# communication.net
KiCad netlist of a schematic drawn in Altium Designer
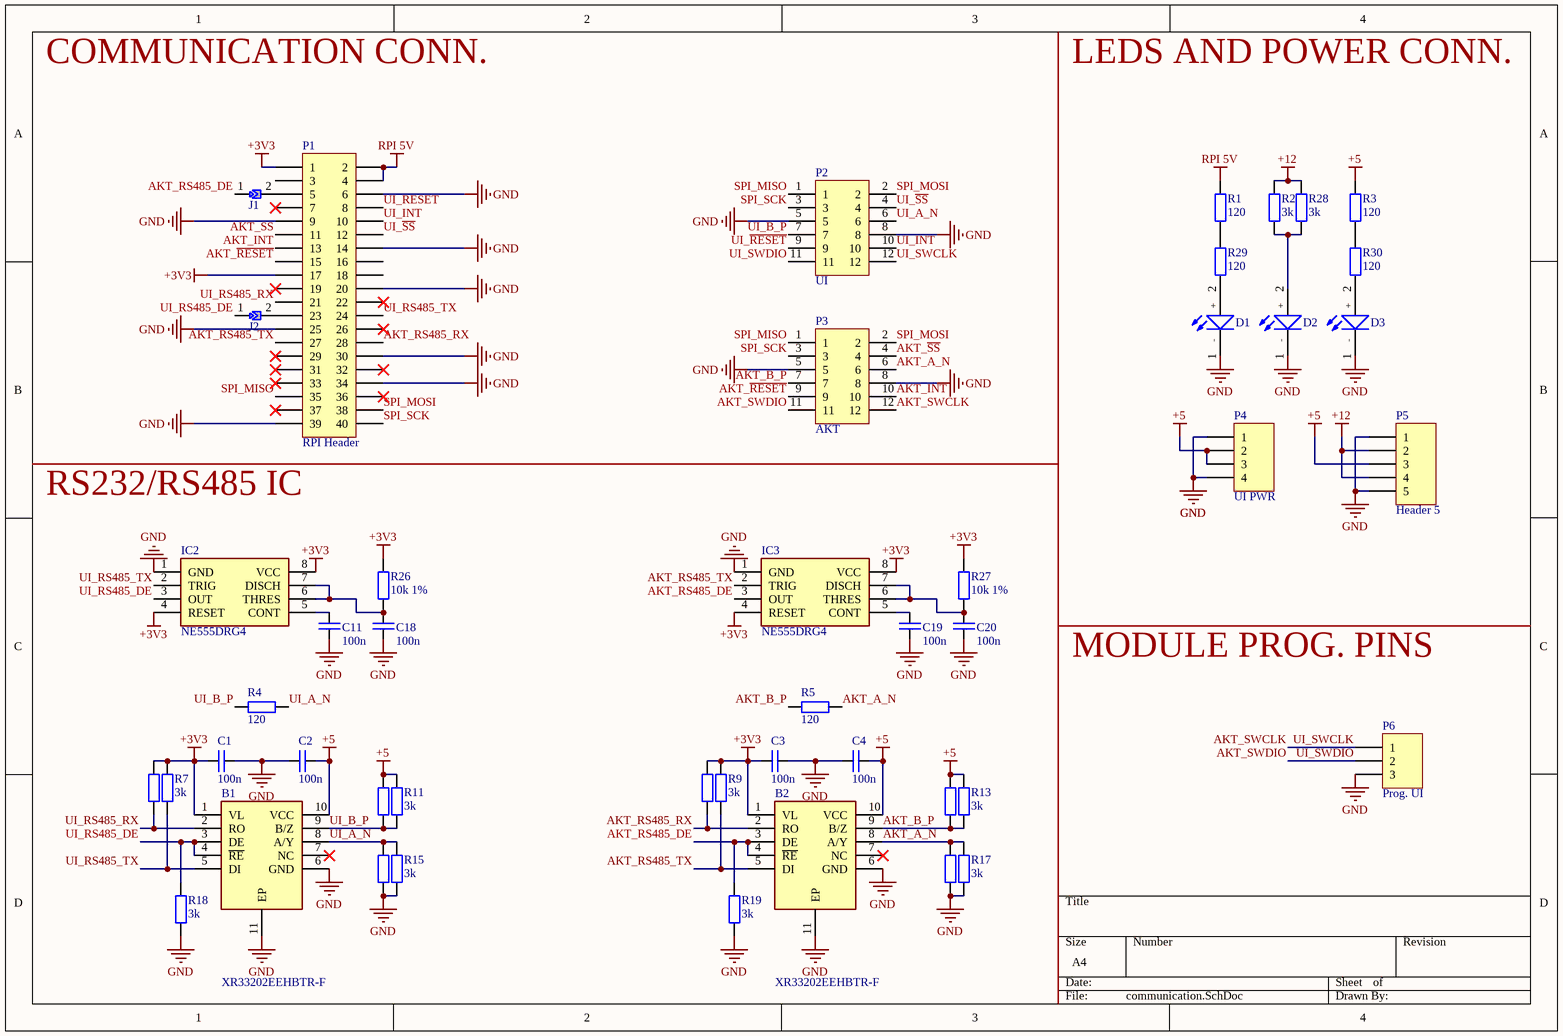
[diagram p0: communication.SchDoc]

(export (version "E")
  (design (tool "Eeschema 10.0.6"))
  (components
    (comp (ref "B1")
      (value "XR33202EEHBTR-F")
      (footprint "SON50P300X300X80-11N-D")
      (description "RS-422/RS-485 Interface IC Wide Supply Trans with I/O Interface")
      (fields (field (name "MOUSER PART NUMBER") "701-XR33202EEHBTR-F"))
      (libsource (lib "components_library") (part "XR33202EEHBTR-F"))
    )
    (comp (ref "B2")
      (value "XR33202EEHBTR-F")
      (footprint "SON50P300X300X80-11N-D")
      (description "RS-422/RS-485 Interface IC Wide Supply Trans with I/O Interface")
      (fields (field (name "MOUSER PART NUMBER") "701-XR33202EEHBTR-F"))
      (libsource (lib "components_library") (part "XR33202EEHBTR-F"))
    )
    (comp (ref "C1")
      (value "100n")
      (footprint "R1005_0402i_L")
      (description "Capacitor")
      (libsource (lib "General") (part "C"))
    )
    (comp (ref "C2")
      (value "100n")
      (footprint "R1005_0402i_L")
      (description "Capacitor")
      (libsource (lib "General") (part "C"))
    )
    (comp (ref "C3")
      (value "100n")
      (footprint "R1005_0402i_L")
      (description "Capacitor")
      (libsource (lib "General") (part "C"))
    )
    (comp (ref "C4")
      (value "100n")
      (footprint "R1005_0402i_L")
      (description "Capacitor")
      (libsource (lib "General") (part "C"))
    )
    (comp (ref "C11")
      (value "100n")
      (footprint "R1005_0402i_L")
      (description "Capacitor")
      (libsource (lib "General") (part "C"))
    )
    (comp (ref "C18")
      (value "100n")
      (footprint "R1005_0402i_L")
      (description "Capacitor")
      (libsource (lib "General") (part "C"))
    )
    (comp (ref "C19")
      (value "100n")
      (footprint "R1005_0402i_L")
      (description "Capacitor")
      (libsource (lib "General") (part "C"))
    )
    (comp (ref "C20")
      (value "100n")
      (footprint "R1005_0402i_L")
      (description "Capacitor")
      (libsource (lib "General") (part "C"))
    )
    (comp (ref "D1") (value "LED") (footprint "LED1608_0603I_L") (libsource (lib "General") (part "LED")))
    (comp (ref "D2") (value "LED") (footprint "LED1608_0603I_L") (libsource (lib "General") (part "LED")))
    (comp (ref "D3") (value "LED") (footprint "LED1608_0603I_L") (libsource (lib "General") (part "LED")))
    (comp (ref "IC2")
      (value "NE555DRG4")
      (footprint "SamacSys:SOIC127P600X175-8N")
      (description "Integrated Circuit")
      (fields (field (name "MOUSER PART NUMBER") "595-NE555DRG4"))
      (libsource (lib "*") (part "NE555DRG4"))
    )
    (comp (ref "IC3")
      (value "NE555DRG4")
      (footprint "SamacSys:SOIC127P600X175-8N")
      (description "Integrated Circuit")
      (fields (field (name "MOUSER PART NUMBER") "595-NE555DRG4"))
      (libsource (lib "*") (part "NE555DRG4"))
    )
    (comp (ref "J1")
      (value "solder_jumper")
      (footprint "solder_jumper_triangle")
      (libsource (lib "components_library") (part "solder_jumper"))
    )
    (comp (ref "J2")
      (value "solder_jumper")
      (footprint "solder_jumper_triangle")
      (libsource (lib "components_library") (part "solder_jumper"))
    )
    (comp (ref "P1")
      (value "RPI Header")
      (footprint "HDR2X20")
      (description "Header, 20-Pin, Dual row")
      (fields (field (name "PUBLISHER") "Altium Limited"))
      (libsource (lib "Miscellaneous Connectors") (part "Header 20X2"))
    )
    (comp (ref "P2")
      (value "UI")
      (footprint "1.27mm SMD conn")
      (libsource (lib "components_library") (part "2x6 THT Header"))
    )
    (comp (ref "P3")
      (value "AKT")
      (footprint "1.27mm SMD conn")
      (libsource (lib "components_library") (part "2x6 THT Header"))
    )
    (comp (ref "P4")
      (value "UI PWR")
      (footprint "HDR1X4")
      (description "Header, 4-Pin")
      (fields (field (name "PUBLISHER") "Altium Limited"))
      (libsource (lib "Miscellaneous Connectors") (part "Header 4"))
    )
    (comp (ref "P5")
      (value "Header 5")
      (footprint "HDR1X5")
      (description "Header, 5-Pin")
      (fields (field (name "PUBLISHER") "Altium Limited"))
      (libsource (lib "Miscellaneous Connectors") (part "Header 5"))
    )
    (comp (ref "P6")
      (value "Prog. UI")
      (footprint "HDR1X3")
      (description "Header, 3-Pin")
      (fields (field (name "PUBLISHER") "Altium Limited"))
      (libsource (lib "Miscellaneous Connectors") (part "Header 3"))
    )
    (comp (ref "R1")
      (value "120")
      (footprint "R1005_0402i_L")
      (description "R")
      (libsource (lib "General") (part "R"))
    )
    (comp (ref "R2")
      (value "3k")
      (footprint "R1005_0402i_L")
      (description "R")
      (libsource (lib "General") (part "R"))
    )
    (comp (ref "R3")
      (value "120")
      (footprint "R1005_0402i_L")
      (description "R")
      (libsource (lib "General") (part "R"))
    )
    (comp (ref "R4")
      (value "120")
      (footprint "R1005_0402i_L")
      (description "R")
      (libsource (lib "General") (part "R"))
    )
    (comp (ref "R5")
      (value "120")
      (footprint "R1005_0402i_L")
      (description "R")
      (libsource (lib "General") (part "R"))
    )
    (comp (ref "R6")
      (value "3k")
      (footprint "R1005_0402i_L")
      (description "R")
      (libsource (lib "General") (part "R"))
    )
    (comp (ref "R7")
      (value "3k")
      (footprint "R1005_0402i_L")
      (description "R")
      (libsource (lib "General") (part "R"))
    )
    (comp (ref "R8")
      (value "3k")
      (footprint "R1005_0402i_L")
      (description "R")
      (libsource (lib "General") (part "R"))
    )
    (comp (ref "R9")
      (value "3k")
      (footprint "R1005_0402i_L")
      (description "R")
      (libsource (lib "General") (part "R"))
    )
    (comp (ref "R10")
      (value "3k")
      (footprint "R1005_0402i_L")
      (description "R")
      (libsource (lib "General") (part "R"))
    )
    (comp (ref "R11")
      (value "3k")
      (footprint "R1005_0402i_L")
      (description "R")
      (libsource (lib "General") (part "R"))
    )
    (comp (ref "R12")
      (value "3k")
      (footprint "R1005_0402i_L")
      (description "R")
      (libsource (lib "General") (part "R"))
    )
    (comp (ref "R13")
      (value "3k")
      (footprint "R1005_0402i_L")
      (description "R")
      (libsource (lib "General") (part "R"))
    )
    (comp (ref "R14")
      (value "3k")
      (footprint "R1005_0402i_L")
      (description "R")
      (libsource (lib "General") (part "R"))
    )
    (comp (ref "R15")
      (value "3k")
      (footprint "R1005_0402i_L")
      (description "R")
      (libsource (lib "General") (part "R"))
    )
    (comp (ref "R16")
      (value "3k")
      (footprint "R1005_0402i_L")
      (description "R")
      (libsource (lib "General") (part "R"))
    )
    (comp (ref "R17")
      (value "3k")
      (footprint "R1005_0402i_L")
      (description "R")
      (libsource (lib "General") (part "R"))
    )
    (comp (ref "R18")
      (value "3k")
      (footprint "R1005_0402i_L")
      (description "R")
      (libsource (lib "General") (part "R"))
    )
    (comp (ref "R19")
      (value "3k")
      (footprint "R1005_0402i_L")
      (description "R")
      (libsource (lib "General") (part "R"))
    )
    (comp (ref "R26")
      (value "10k 1%")
      (footprint "R1005_0402i_L")
      (description "R")
      (libsource (lib "General") (part "R"))
    )
    (comp (ref "R27")
      (value "10k 1%")
      (footprint "R1005_0402i_L")
      (description "R")
      (libsource (lib "General") (part "R"))
    )
    (comp (ref "R28")
      (value "3k")
      (footprint "R1005_0402i_L")
      (description "R")
      (libsource (lib "General") (part "R"))
    )
    (comp (ref "R29")
      (value "120")
      (footprint "R1005_0402i_L")
      (description "R")
      (libsource (lib "General") (part "R"))
    )
    (comp (ref "R30")
      (value "120")
      (footprint "R1005_0402i_L")
      (description "R")
      (libsource (lib "General") (part "R"))
    )
  )
  (nets
    (net (code "1") (name "+3V3") (class "Default")
      (node (ref "B1") (pin "1") (pinfunction "VL_1") (pintype "passive"))
      (node (ref "B2") (pin "1") (pinfunction "VL_1") (pintype "passive"))
      (node (ref "C1") (pin "1") (pinfunction "1_1") (pintype "passive"))
      (node (ref "C3") (pin "1") (pinfunction "1_1") (pintype "passive"))
      (node (ref "IC2") (pin "4") (pinfunction "RESET_4") (pintype "passive"))
      (node (ref "IC2") (pin "8") (pinfunction "VCC_8") (pintype "passive"))
      (node (ref "IC3") (pin "4") (pinfunction "RESET_4") (pintype "passive"))
      (node (ref "IC3") (pin "8") (pinfunction "VCC_8") (pintype "passive"))
      (node (ref "P1") (pin "1") (pinfunction "1_1") (pintype "passive"))
      (node (ref "P1") (pin "17") (pinfunction "17_17") (pintype "passive"))
      (node (ref "R26") (pin "2") (pintype "passive"))
      (node (ref "R27") (pin "2") (pintype "passive"))
      (node (ref "R6") (pin "2") (pintype "passive"))
      (node (ref "R7") (pin "2") (pintype "passive"))
      (node (ref "R8") (pin "2") (pintype "passive"))
      (node (ref "R9") (pin "2") (pintype "passive"))
    )
    (net (code "2") (name "+5") (class "Default")
      (node (ref "B1") (pin "10") (pinfunction "VCC_10") (pintype "passive"))
      (node (ref "B2") (pin "10") (pinfunction "VCC_10") (pintype "passive"))
      (node (ref "C2") (pin "2") (pinfunction "2_2") (pintype "passive"))
      (node (ref "C4") (pin "2") (pinfunction "2_2") (pintype "passive"))
      (node (ref "P4") (pin "2") (pinfunction "2_2") (pintype "passive"))
      (node (ref "P4") (pin "3") (pinfunction "3_3") (pintype "passive"))
      (node (ref "P5") (pin "3") (pinfunction "3_3") (pintype "passive"))
      (node (ref "R10") (pin "2") (pintype "passive"))
      (node (ref "R11") (pin "2") (pintype "passive"))
      (node (ref "R12") (pin "2") (pintype "passive"))
      (node (ref "R13") (pin "2") (pintype "passive"))
      (node (ref "R3") (pin "1") (pintype "passive"))
    )
    (net (code "3") (name "+12") (class "Default")
      (node (ref "P5") (pin "2") (pinfunction "2_2") (pintype "passive"))
      (node (ref "P5") (pin "4") (pinfunction "4_4") (pintype "passive"))
      (node (ref "R2") (pin "1") (pintype "passive"))
      (node (ref "R28") (pin "1") (pintype "passive"))
    )
    (net (code "4") (name "/AKT_A_N") (class "Default")
      (node (ref "B2") (pin "8") (pinfunction "A/Y_8") (pintype "passive"))
      (node (ref "P3") (pin "6") (pinfunction "6_6") (pintype "passive"))
      (node (ref "R16") (pin "2") (pintype "passive"))
      (node (ref "R17") (pin "2") (pintype "passive"))
      (node (ref "R5") (pin "2") (pintype "passive"))
    )
    (net (code "5") (name "/AKT_B_P") (class "Default")
      (node (ref "B2") (pin "9") (pinfunction "B/Z_9") (pintype "passive"))
      (node (ref "P3") (pin "7") (pinfunction "7_7") (pintype "passive"))
      (node (ref "R12") (pin "1") (pintype "passive"))
      (node (ref "R13") (pin "1") (pintype "passive"))
      (node (ref "R5") (pin "1") (pintype "passive"))
    )
    (net (code "6") (name "/AKT_INT") (class "Default")
      (node (ref "P1") (pin "13") (pinfunction "13_13") (pintype "passive"))
      (node (ref "P3") (pin "10") (pinfunction "10_10") (pintype "passive"))
    )
    (net (code "7") (name "/AKT_RS485_DE") (class "Default")
      (node (ref "B2") (pin "3") (pinfunction "DE_3") (pintype "passive"))
      (node (ref "B2") (pin "4") (pinfunction "~{RE}_4") (pintype "passive"))
      (node (ref "IC3") (pin "3") (pinfunction "OUT_3") (pintype "passive"))
      (node (ref "J1") (pin "1") (pintype "passive"))
      (node (ref "R19") (pin "2") (pintype "passive"))
    )
    (net (code "8") (name "/AKT_RS485_RX") (class "Default")
      (node (ref "B2") (pin "2") (pinfunction "RO_2") (pintype "passive"))
      (node (ref "P1") (pin "28") (pinfunction "28_28") (pintype "passive"))
      (node (ref "R8") (pin "1") (pintype "passive"))
    )
    (net (code "9") (name "/AKT_RS485_TX") (class "Default")
      (node (ref "B2") (pin "5") (pinfunction "DI_5") (pintype "passive"))
      (node (ref "IC3") (pin "2") (pinfunction "TRIG_2") (pintype "passive"))
      (node (ref "P1") (pin "27") (pinfunction "27_27") (pintype "passive"))
      (node (ref "R9") (pin "1") (pintype "passive"))
    )
    (net (code "10") (name "/AKT_SWCLK") (class "Default")
      (node (ref "P2") (pin "12") (pinfunction "12_12") (pintype "passive"))
      (node (ref "P3") (pin "12") (pinfunction "12_12") (pintype "passive"))
      (node (ref "P6") (pin "1") (pinfunction "1_1") (pintype "passive"))
    )
    (net (code "11") (name "/AKT_SWDIO") (class "Default")
      (node (ref "P2") (pin "11") (pinfunction "11_11") (pintype "passive"))
      (node (ref "P3") (pin "11") (pinfunction "11_11") (pintype "passive"))
      (node (ref "P6") (pin "2") (pinfunction "2_2") (pintype "passive"))
    )
    (net (code "12") (name "/AKT_~{RESET}") (class "Default")
      (node (ref "P1") (pin "15") (pinfunction "15_15") (pintype "passive"))
      (node (ref "P3") (pin "9") (pinfunction "9_9") (pintype "passive"))
    )
    (net (code "13") (name "/AKT_~{SS}") (class "Default")
      (node (ref "P1") (pin "11") (pinfunction "11_11") (pintype "passive"))
      (node (ref "P3") (pin "4") (pinfunction "4_4") (pintype "passive"))
    )
    (net (code "14") (name "/SPI_MISO") (class "Default")
      (node (ref "P1") (pin "35") (pinfunction "35_35") (pintype "passive"))
      (node (ref "P2") (pin "1") (pinfunction "1_1") (pintype "passive"))
      (node (ref "P3") (pin "1") (pinfunction "1_1") (pintype "passive"))
    )
    (net (code "15") (name "/SPI_MOSI") (class "Default")
      (node (ref "P1") (pin "38") (pinfunction "38_38") (pintype "passive"))
      (node (ref "P2") (pin "2") (pinfunction "2_2") (pintype "passive"))
      (node (ref "P3") (pin "2") (pinfunction "2_2") (pintype "passive"))
    )
    (net (code "16") (name "/SPI_SCK") (class "Default")
      (node (ref "P1") (pin "40") (pinfunction "40_40") (pintype "passive"))
      (node (ref "P2") (pin "3") (pinfunction "3_3") (pintype "passive"))
      (node (ref "P3") (pin "3") (pinfunction "3_3") (pintype "passive"))
    )
    (net (code "17") (name "/UI_A_N") (class "Default")
      (node (ref "B1") (pin "8") (pinfunction "A/Y_8") (pintype "passive"))
      (node (ref "P2") (pin "6") (pinfunction "6_6") (pintype "passive"))
      (node (ref "R14") (pin "2") (pintype "passive"))
      (node (ref "R15") (pin "2") (pintype "passive"))
      (node (ref "R4") (pin "2") (pintype "passive"))
    )
    (net (code "18") (name "/UI_B_P") (class "Default")
      (node (ref "B1") (pin "9") (pinfunction "B/Z_9") (pintype "passive"))
      (node (ref "P2") (pin "7") (pinfunction "7_7") (pintype "passive"))
      (node (ref "R10") (pin "1") (pintype "passive"))
      (node (ref "R11") (pin "1") (pintype "passive"))
      (node (ref "R4") (pin "1") (pintype "passive"))
    )
    (net (code "19") (name "/UI_INT") (class "Default")
      (node (ref "P1") (pin "10") (pinfunction "10_10") (pintype "passive"))
      (node (ref "P2") (pin "10") (pinfunction "10_10") (pintype "passive"))
    )
    (net (code "20") (name "/UI_RS485_DE") (class "Default")
      (node (ref "B1") (pin "3") (pinfunction "DE_3") (pintype "passive"))
      (node (ref "B1") (pin "4") (pinfunction "~{RE}_4") (pintype "passive"))
      (node (ref "IC2") (pin "3") (pinfunction "OUT_3") (pintype "passive"))
      (node (ref "J2") (pin "1") (pintype "passive"))
      (node (ref "R18") (pin "2") (pintype "passive"))
    )
    (net (code "21") (name "/UI_RS485_RX") (class "Default")
      (node (ref "B1") (pin "2") (pinfunction "RO_2") (pintype "passive"))
      (node (ref "P1") (pin "21") (pinfunction "21_21") (pintype "passive"))
      (node (ref "R6") (pin "1") (pintype "passive"))
    )
    (net (code "22") (name "/UI_RS485_TX") (class "Default")
      (node (ref "B1") (pin "5") (pinfunction "DI_5") (pintype "passive"))
      (node (ref "IC2") (pin "2") (pinfunction "TRIG_2") (pintype "passive"))
      (node (ref "P1") (pin "24") (pinfunction "24_24") (pintype "passive"))
      (node (ref "R7") (pin "1") (pintype "passive"))
    )
    (net (code "23") (name "/UI_~{RESET}") (class "Default")
      (node (ref "P1") (pin "8") (pinfunction "8_8") (pintype "passive"))
      (node (ref "P2") (pin "9") (pinfunction "9_9") (pintype "passive"))
    )
    (net (code "24") (name "/UI_~{SS}") (class "Default")
      (node (ref "P1") (pin "12") (pinfunction "12_12") (pintype "passive"))
      (node (ref "P2") (pin "4") (pinfunction "4_4") (pintype "passive"))
    )
    (net (code "25") (name "GND") (class "Default")
      (node (ref "B1") (pin "11") (pinfunction "EP_11") (pintype "passive"))
      (node (ref "B1") (pin "6") (pinfunction "GND_6") (pintype "passive"))
      (node (ref "B2") (pin "11") (pinfunction "EP_11") (pintype "passive"))
      (node (ref "B2") (pin "6") (pinfunction "GND_6") (pintype "passive"))
      (node (ref "C1") (pin "2") (pinfunction "2_2") (pintype "passive"))
      (node (ref "C11") (pin "2") (pinfunction "2_2") (pintype "passive"))
      (node (ref "C18") (pin "2") (pinfunction "2_2") (pintype "passive"))
      (node (ref "C19") (pin "2") (pinfunction "2_2") (pintype "passive"))
      (node (ref "C2") (pin "1") (pinfunction "1_1") (pintype "passive"))
      (node (ref "C20") (pin "2") (pinfunction "2_2") (pintype "passive"))
      (node (ref "C3") (pin "2") (pinfunction "2_2") (pintype "passive"))
      (node (ref "C4") (pin "1") (pinfunction "1_1") (pintype "passive"))
      (node (ref "D1") (pin "1") (pinfunction "-_1") (pintype "passive"))
      (node (ref "D2") (pin "1") (pinfunction "-_1") (pintype "passive"))
      (node (ref "D3") (pin "1") (pinfunction "-_1") (pintype "passive"))
      (node (ref "IC2") (pin "1") (pinfunction "GND_1") (pintype "passive"))
      (node (ref "IC3") (pin "1") (pinfunction "GND_1") (pintype "passive"))
      (node (ref "P1") (pin "14") (pinfunction "14_14") (pintype "passive"))
      (node (ref "P1") (pin "20") (pinfunction "20_20") (pintype "passive"))
      (node (ref "P1") (pin "25") (pinfunction "25_25") (pintype "passive"))
      (node (ref "P1") (pin "30") (pinfunction "30_30") (pintype "passive"))
      (node (ref "P1") (pin "34") (pinfunction "34_34") (pintype "passive"))
      (node (ref "P1") (pin "39") (pinfunction "39_39") (pintype "passive"))
      (node (ref "P1") (pin "6") (pinfunction "6_6") (pintype "passive"))
      (node (ref "P1") (pin "9") (pinfunction "9_9") (pintype "passive"))
      (node (ref "P2") (pin "5") (pinfunction "5_5") (pintype "passive"))
      (node (ref "P2") (pin "8") (pinfunction "8_8") (pintype "passive"))
      (node (ref "P3") (pin "5") (pinfunction "5_5") (pintype "passive"))
      (node (ref "P3") (pin "8") (pinfunction "8_8") (pintype "passive"))
      (node (ref "P4") (pin "1") (pinfunction "1_1") (pintype "passive"))
      (node (ref "P4") (pin "4") (pinfunction "4_4") (pintype "passive"))
      (node (ref "P5") (pin "1") (pinfunction "1_1") (pintype "passive"))
      (node (ref "P5") (pin "5") (pinfunction "5_5") (pintype "passive"))
      (node (ref "P6") (pin "3") (pinfunction "3_3") (pintype "passive"))
      (node (ref "R14") (pin "1") (pintype "passive"))
      (node (ref "R15") (pin "1") (pintype "passive"))
      (node (ref "R16") (pin "1") (pintype "passive"))
      (node (ref "R17") (pin "1") (pintype "passive"))
      (node (ref "R18") (pin "1") (pintype "passive"))
      (node (ref "R19") (pin "1") (pintype "passive"))
    )
    (net (code "26") (name "Net-(D1-+)") (class "Default")
      (node (ref "D1") (pin "2") (pinfunction "+_2") (pintype "passive"))
      (node (ref "R29") (pin "2") (pintype "passive"))
    )
    (net (code "27") (name "Net-(D2-+)") (class "Default")
      (node (ref "D2") (pin "2") (pinfunction "+_2") (pintype "passive"))
      (node (ref "R2") (pin "2") (pintype "passive"))
      (node (ref "R28") (pin "2") (pintype "passive"))
    )
    (net (code "28") (name "Net-(D3-+)") (class "Default")
      (node (ref "D3") (pin "2") (pinfunction "+_2") (pintype "passive"))
      (node (ref "R30") (pin "2") (pintype "passive"))
    )
    (net (code "29") (name "Net-(IC2-CONT)") (class "Default")
      (node (ref "C11") (pin "1") (pinfunction "1_1") (pintype "passive"))
      (node (ref "IC2") (pin "5") (pinfunction "CONT_5") (pintype "passive"))
    )
    (net (code "30") (name "Net-(IC2-DISCH)") (class "Default")
      (node (ref "C18") (pin "1") (pinfunction "1_1") (pintype "passive"))
      (node (ref "IC2") (pin "6") (pinfunction "THRES_6") (pintype "passive"))
      (node (ref "IC2") (pin "7") (pinfunction "DISCH_7") (pintype "passive"))
      (node (ref "R26") (pin "1") (pintype "passive"))
    )
    (net (code "31") (name "Net-(IC3-CONT)") (class "Default")
      (node (ref "C19") (pin "1") (pinfunction "1_1") (pintype "passive"))
      (node (ref "IC3") (pin "5") (pinfunction "CONT_5") (pintype "passive"))
    )
    (net (code "32") (name "Net-(IC3-DISCH)") (class "Default")
      (node (ref "C20") (pin "1") (pinfunction "1_1") (pintype "passive"))
      (node (ref "IC3") (pin "6") (pinfunction "THRES_6") (pintype "passive"))
      (node (ref "IC3") (pin "7") (pinfunction "DISCH_7") (pintype "passive"))
      (node (ref "R27") (pin "1") (pintype "passive"))
    )
    (net (code "33") (name "Net-(J1-Pad2)") (class "Default")
      (node (ref "J1") (pin "2") (pintype "passive"))
      (node (ref "P1") (pin "5") (pinfunction "5_5") (pintype "passive"))
    )
    (net (code "34") (name "Net-(J2-Pad2)") (class "Default")
      (node (ref "J2") (pin "2") (pintype "passive"))
      (node (ref "P1") (pin "23") (pinfunction "23_23") (pintype "passive"))
    )
    (net (code "35") (name "Net-(R1-Pad2)") (class "Default")
      (node (ref "R1") (pin "2") (pintype "passive"))
      (node (ref "R29") (pin "1") (pintype "passive"))
    )
    (net (code "36") (name "Net-(R3-Pad2)") (class "Default")
      (node (ref "R3") (pin "2") (pintype "passive"))
      (node (ref "R30") (pin "1") (pintype "passive"))
    )
    (net (code "37") (name "RPI 5V") (class "Default")
      (node (ref "P1") (pin "2") (pinfunction "2_2") (pintype "passive"))
      (node (ref "P1") (pin "4") (pinfunction "4_4") (pintype "passive"))
      (node (ref "R1") (pin "1") (pintype "passive"))
    )
    (net (code "38") (name "unconnected-(B1-NC-Pad7)") (class "Default")
      (node (ref "B1") (pin "7") (pinfunction "NC_7") (pintype "passive+no_connect"))
    )
    (net (code "39") (name "unconnected-(B2-NC-Pad7)") (class "Default")
      (node (ref "B2") (pin "7") (pinfunction "NC_7") (pintype "passive+no_connect"))
    )
    (net (code "40") (name "unconnected-(P1-Pad3)") (class "Default")
      (node (ref "P1") (pin "3") (pinfunction "3_3") (pintype "passive"))
    )
    (net (code "41") (name "unconnected-(P1-Pad7)") (class "Default")
      (node (ref "P1") (pin "7") (pinfunction "7_7") (pintype "passive+no_connect"))
    )
    (net (code "42") (name "unconnected-(P1-Pad16)") (class "Default")
      (node (ref "P1") (pin "16") (pinfunction "16_16") (pintype "passive"))
    )
    (net (code "43") (name "unconnected-(P1-Pad18)") (class "Default")
      (node (ref "P1") (pin "18") (pinfunction "18_18") (pintype "passive"))
    )
    (net (code "44") (name "unconnected-(P1-Pad19)") (class "Default")
      (node (ref "P1") (pin "19") (pinfunction "19_19") (pintype "passive+no_connect"))
    )
    (net (code "45") (name "unconnected-(P1-Pad22)") (class "Default")
      (node (ref "P1") (pin "22") (pinfunction "22_22") (pintype "passive+no_connect"))
    )
    (net (code "46") (name "unconnected-(P1-Pad26)") (class "Default")
      (node (ref "P1") (pin "26") (pinfunction "26_26") (pintype "passive+no_connect"))
    )
    (net (code "47") (name "unconnected-(P1-Pad29)") (class "Default")
      (node (ref "P1") (pin "29") (pinfunction "29_29") (pintype "passive+no_connect"))
    )
    (net (code "48") (name "unconnected-(P1-Pad31)") (class "Default")
      (node (ref "P1") (pin "31") (pinfunction "31_31") (pintype "passive+no_connect"))
    )
    (net (code "49") (name "unconnected-(P1-Pad32)") (class "Default")
      (node (ref "P1") (pin "32") (pinfunction "32_32") (pintype "passive+no_connect"))
    )
    (net (code "50") (name "unconnected-(P1-Pad33)") (class "Default")
      (node (ref "P1") (pin "33") (pinfunction "33_33") (pintype "passive+no_connect"))
    )
    (net (code "51") (name "unconnected-(P1-Pad36)") (class "Default")
      (node (ref "P1") (pin "36") (pinfunction "36_36") (pintype "passive+no_connect"))
    )
    (net (code "52") (name "unconnected-(P1-Pad37)") (class "Default")
      (node (ref "P1") (pin "37") (pinfunction "37_37") (pintype "passive+no_connect"))
    )
  )
)
